# Power_Distribution_-_Pi.net
KiCad netlist of a schematic drawn in Altium Designer
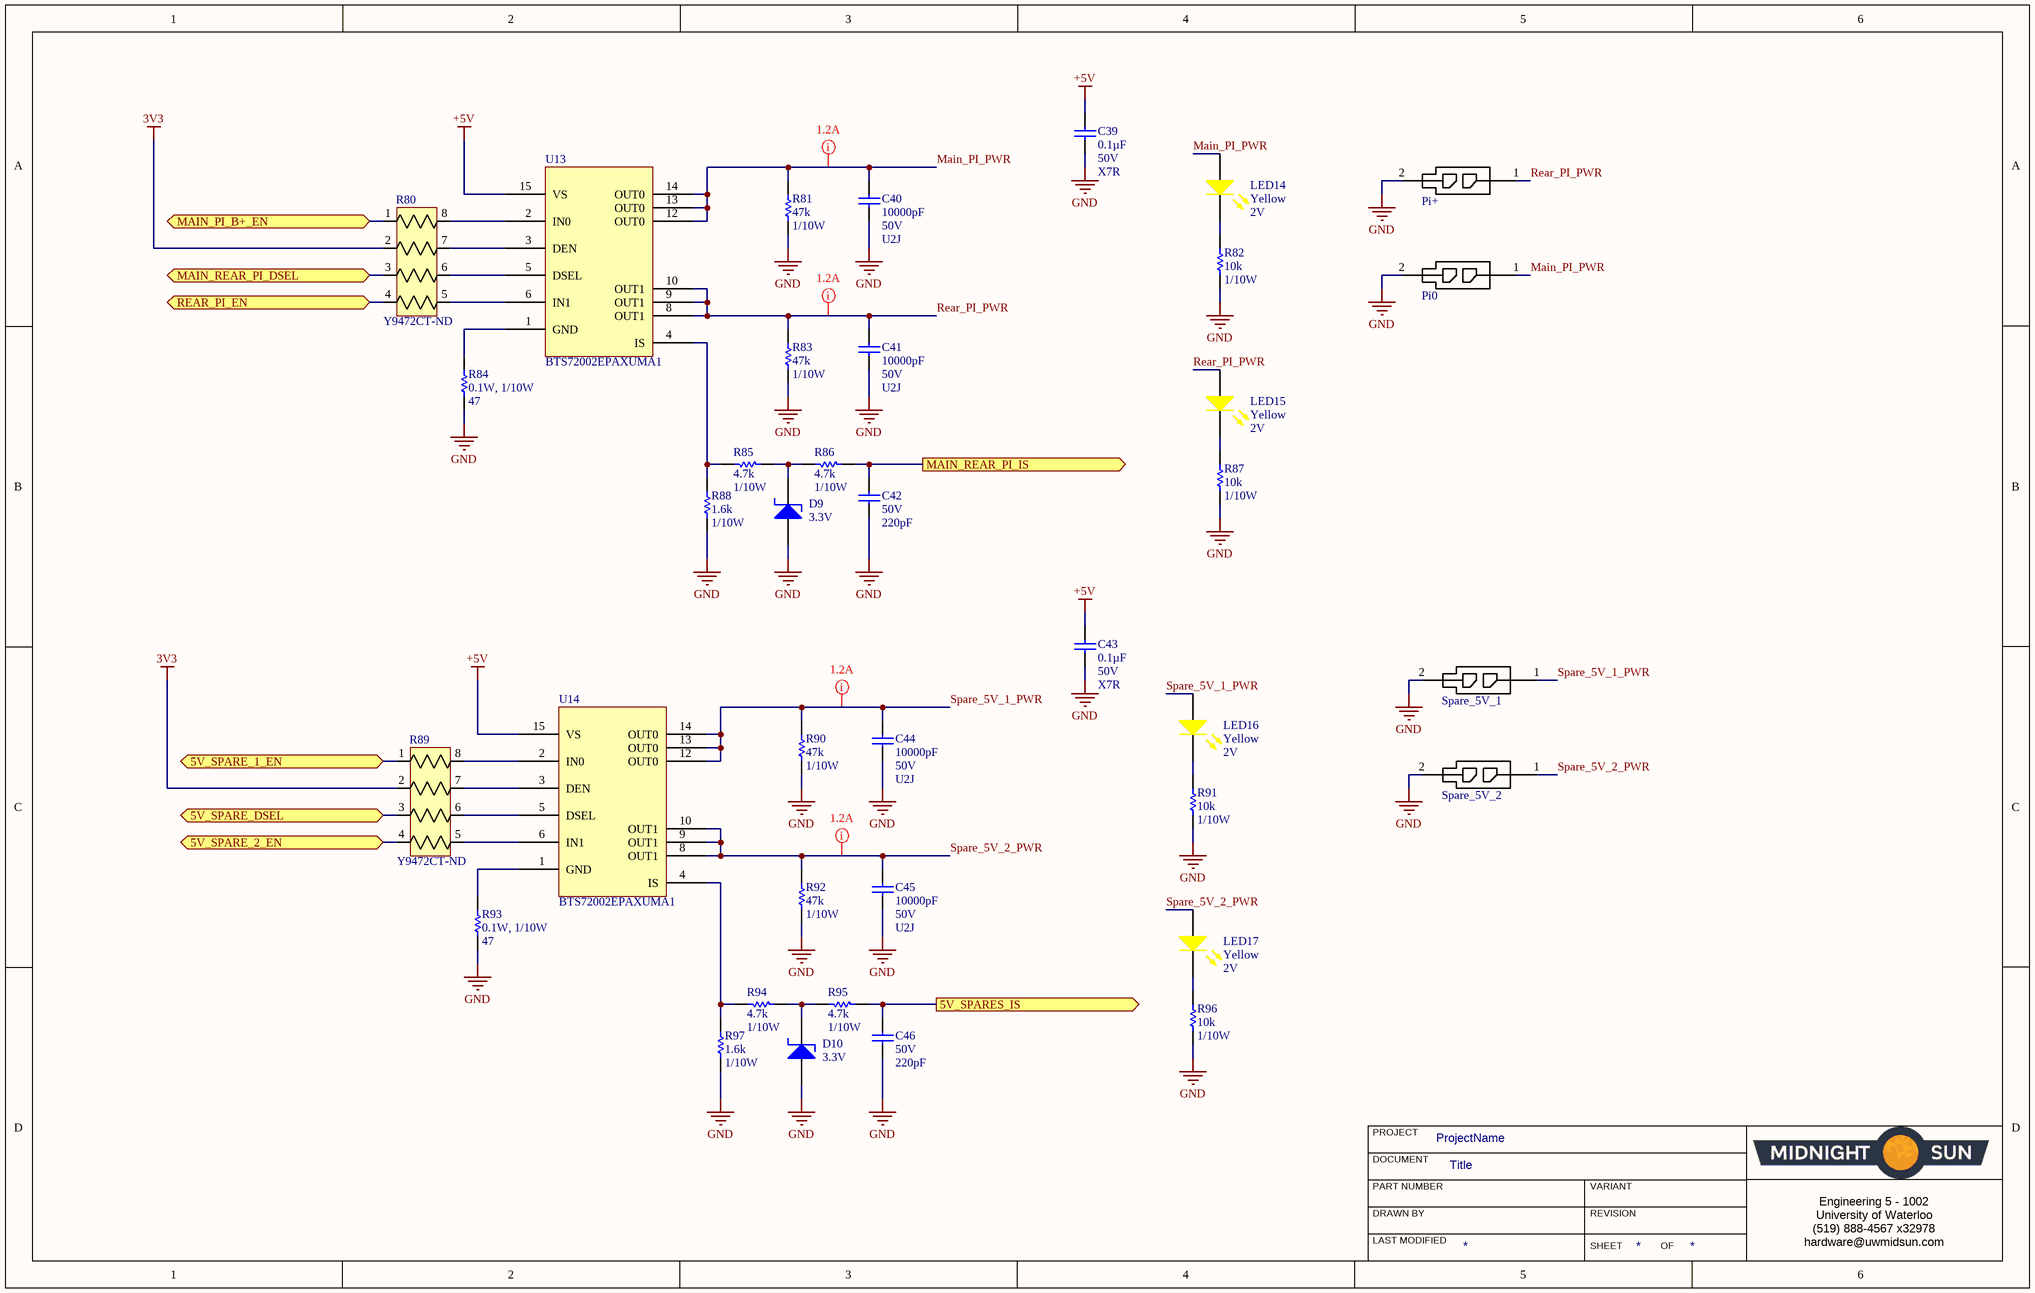
[diagram p0: Power Distribution - Pi.SchDoc]

(export (version "E")
  (design (tool "Eeschema 10.0.6"))
  (components
    (comp (ref "C39")
      (value "CAP CER 0.1UF 50V 10% X7R 0603")
      (footprint "CAP, 0603")
      (description "0.10µF ±10% 50V Ceramic Capacitor X7R 0603 (1608 Metric)")
      (fields
        (field (name "TOLERANCE") "±10%")
        (field (name "CAPACITANCE") "0.1µF")
        (field (name "VOLTAGE") "50V")
        (field (name "TEMPERATURE COEFFICIENT") "X7R")
      )
      (libsource (lib "Schematic Diagrams") (part "CAP CER 0.1UF 50V 10% X7R 0603"))
    )
    (comp (ref "C40")
      (value "CAP CER 10nF 50V 5% X7R 0603")
      (footprint "CAP, 0603")
      (description "10000pF ±5% 50V Ceramic Capacitor U2J 0603 (1608 Metric)")
      (fields
        (field (name "TOLERANCE") "±5%")
        (field (name "CAPACITANCE") "10000pF")
        (field (name "VOLTAGE") "50V")
        (field (name "TEMPERATURE COEFFICIENT") "U2J")
      )
      (libsource (lib "Schematic Diagrams") (part "CAP CER 10nF 50V 5% X7R 0603"))
    )
    (comp (ref "C41")
      (value "CAP CER 10nF 50V 5% X7R 0603")
      (footprint "CAP, 0603")
      (description "10000pF ±5% 50V Ceramic Capacitor U2J 0603 (1608 Metric)")
      (fields
        (field (name "TOLERANCE") "±5%")
        (field (name "CAPACITANCE") "10000pF")
        (field (name "VOLTAGE") "50V")
        (field (name "TEMPERATURE COEFFICIENT") "U2J")
      )
      (libsource (lib "Schematic Diagrams") (part "CAP CER 10nF 50V 5% X7R 0603"))
    )
    (comp (ref "C42")
      (value "CAP CER 220PF 50V C0G/NP0 0603")
      (footprint "CAP, 0603")
      (description "220pF ±5% 50V Ceramic Capacitor C0G, NP0 0603 (1608 Metric)")
      (fields
        (field (name "MANUFACTURER") "KEMET")
        (field (name "TOLERANCE") "5%")
        (field (name "VOLTAGE RATING") "50V")
        (field (name "CAPACITANCE") "220pF")
      )
      (libsource (lib "Schematic Diagrams") (part "CAP CER 220PF 50V C0G/NP0 0603"))
    )
    (comp (ref "C43")
      (value "CAP CER 0.1UF 50V 10% X7R 0603")
      (footprint "CAP, 0603")
      (description "0.10µF ±10% 50V Ceramic Capacitor X7R 0603 (1608 Metric)")
      (fields
        (field (name "TOLERANCE") "±10%")
        (field (name "CAPACITANCE") "0.1µF")
        (field (name "VOLTAGE") "50V")
        (field (name "TEMPERATURE COEFFICIENT") "X7R")
      )
      (libsource (lib "Schematic Diagrams") (part "CAP CER 0.1UF 50V 10% X7R 0603"))
    )
    (comp (ref "C44")
      (value "CAP CER 10nF 50V 5% X7R 0603")
      (footprint "CAP, 0603")
      (description "10000pF ±5% 50V Ceramic Capacitor U2J 0603 (1608 Metric)")
      (fields
        (field (name "TOLERANCE") "±5%")
        (field (name "CAPACITANCE") "10000pF")
        (field (name "VOLTAGE") "50V")
        (field (name "TEMPERATURE COEFFICIENT") "U2J")
      )
      (libsource (lib "Schematic Diagrams") (part "CAP CER 10nF 50V 5% X7R 0603"))
    )
    (comp (ref "C45")
      (value "CAP CER 10nF 50V 5% X7R 0603")
      (footprint "CAP, 0603")
      (description "10000pF ±5% 50V Ceramic Capacitor U2J 0603 (1608 Metric)")
      (fields
        (field (name "TOLERANCE") "±5%")
        (field (name "CAPACITANCE") "10000pF")
        (field (name "VOLTAGE") "50V")
        (field (name "TEMPERATURE COEFFICIENT") "U2J")
      )
      (libsource (lib "Schematic Diagrams") (part "CAP CER 10nF 50V 5% X7R 0603"))
    )
    (comp (ref "C46")
      (value "CAP CER 220PF 50V C0G/NP0 0603")
      (footprint "CAP, 0603")
      (description "220pF ±5% 50V Ceramic Capacitor C0G, NP0 0603 (1608 Metric)")
      (fields
        (field (name "MANUFACTURER") "KEMET")
        (field (name "TOLERANCE") "5%")
        (field (name "VOLTAGE RATING") "50V")
        (field (name "CAPACITANCE") "220pF")
      )
      (libsource (lib "Schematic Diagrams") (part "CAP CER 220PF 50V C0G/NP0 0603"))
    )
    (comp (ref "D9")
      (value "DIODE ZENER 3.3V 200MW SOD323")
      (footprint "sod-323")
      (description "Zener Diode 3.3V 200mW ±5% Surface Mount SOD-323")
      (fields (field (name "VOLTAGE") "3.3V"))
      (libsource (lib "Schematic Diagrams") (part "DIODE ZENER 3.3V 200MW SOD323"))
    )
    (comp (ref "D10")
      (value "DIODE ZENER 3.3V 200MW SOD323")
      (footprint "sod-323")
      (description "Zener Diode 3.3V 200mW ±5% Surface Mount SOD-323")
      (fields (field (name "VOLTAGE") "3.3V"))
      (libsource (lib "Schematic Diagrams") (part "DIODE ZENER 3.3V 200MW SOD323"))
    )
    (comp (ref "LED14")
      (value "LED YELLOW CLEAR 2.1V 0603")
      (footprint "LED_0603")
      (description "Yellow 590nm LED Indication - Discrete 2V 0603 (1608 Metric)")
      (fields
        (field (name "MANUFACTURER") "Wurth Electronics Inc.")
        (field (name "MANUFACTURER PART NUMBER") "150060YS75000")
        (field (name "COLOR") "Yellow")
        (field (name "VOLTAGE - FORWARD (VF) (TYP)") "2V")
      )
      (libsource (lib "Schematic Diagrams") (part "LED YELLOW CLEAR 2.1V 0603"))
    )
    (comp (ref "LED15")
      (value "LED YELLOW CLEAR 2.1V 0603")
      (footprint "LED_0603")
      (description "Yellow 590nm LED Indication - Discrete 2V 0603 (1608 Metric)")
      (fields
        (field (name "MANUFACTURER") "Wurth Electronics Inc.")
        (field (name "MANUFACTURER PART NUMBER") "150060YS75000")
        (field (name "COLOR") "Yellow")
        (field (name "VOLTAGE - FORWARD (VF) (TYP)") "2V")
      )
      (libsource (lib "Schematic Diagrams") (part "LED YELLOW CLEAR 2.1V 0603"))
    )
    (comp (ref "LED16")
      (value "LED YELLOW CLEAR 2.1V 0603")
      (footprint "LED_0603")
      (description "Yellow 590nm LED Indication - Discrete 2V 0603 (1608 Metric)")
      (fields
        (field (name "MANUFACTURER") "Wurth Electronics Inc.")
        (field (name "MANUFACTURER PART NUMBER") "150060YS75000")
        (field (name "COLOR") "Yellow")
        (field (name "VOLTAGE - FORWARD (VF) (TYP)") "2V")
      )
      (libsource (lib "Schematic Diagrams") (part "LED YELLOW CLEAR 2.1V 0603"))
    )
    (comp (ref "LED17")
      (value "LED YELLOW CLEAR 2.1V 0603")
      (footprint "LED_0603")
      (description "Yellow 590nm LED Indication - Discrete 2V 0603 (1608 Metric)")
      (fields
        (field (name "MANUFACTURER") "Wurth Electronics Inc.")
        (field (name "MANUFACTURER PART NUMBER") "150060YS75000")
        (field (name "COLOR") "Yellow")
        (field (name "VOLTAGE - FORWARD (VF) (TYP)") "2V")
      )
      (libsource (lib "Schematic Diagrams") (part "LED YELLOW CLEAR 2.1V 0603"))
    )
    (comp (ref "Pi+")
      (value "CONN 2POS MICRO-FIT 3mm")
      (footprint "CONN, 2POS MICRO-FIT")
      (description "Connector Header Through Hole 2 position")
      (fields (field (name "MANUFACTURER") "Molex") (field (name "MANUFACTURER PART NUMBER") "43045-0227"))
      (libsource (lib "Schematic Diagrams") (part "CONN 2POS MICRO-FIT 3mm"))
    )
    (comp (ref "Pi0")
      (value "CONN 2POS MICRO-FIT 3mm")
      (footprint "CONN, 2POS MICRO-FIT")
      (description "Connector Header Through Hole 2 position")
      (fields (field (name "MANUFACTURER") "Molex") (field (name "MANUFACTURER PART NUMBER") "43045-0227"))
      (libsource (lib "Schematic Diagrams") (part "CONN 2POS MICRO-FIT 3mm"))
    )
    (comp (ref "R80")
      (value "RES ARRAY 4 RES 4.7K OHM 1206")
      (footprint "RES ARRAY 4RES 1206")
      (fields (field (name "TOLERANCE") "±5%") (field (name "SUPPLIER PART NUMBER 1") "Y9472CT-ND"))
      (libsource (lib "Schematic Diagrams") (part "RES ARRAY 4 RES 4.7K OHM 1206"))
    )
    (comp (ref "R81")
      (value "RES 47K OHM 1% 1/10W 0603")
      (footprint "RES, 0603")
      (description "47 kOhms ±1% 0.1W, 1/10W Chip Resistor 0603 (1608 Metric) Automotive AEC-Q200 Thick Film")
      (fields
        (field (name "MANUFACTURER") "Panasonic")
        (field (name "MANUFACTURER PART NUMBER") "ERJ3EKF4702V")
        (field (name "RESISTANCE") "47k")
        (field (name "POWER RATING") "1/10W")
      )
      (libsource (lib "Schematic Diagrams") (part "RES 47K OHM 1% 1/10W 0603"))
    )
    (comp (ref "R82")
      (value "RES 10K OHM 1% 1/10W 0603")
      (footprint "RES, 0603")
      (description "RES SMD 10K OHM 1% 1/10W 0603")
      (fields
        (field (name "TOLERANCE") "±1%")
        (field (name "RESISTANCE") "10k")
        (field (name "POWER") "1/10W")
      )
      (libsource (lib "Schematic Diagrams") (part "RES 10K OHM 1% 1/10W 0603"))
    )
    (comp (ref "R83")
      (value "RES 47K OHM 1% 1/10W 0603")
      (footprint "RES, 0603")
      (description "47 kOhms ±1% 0.1W, 1/10W Chip Resistor 0603 (1608 Metric) Automotive AEC-Q200 Thick Film")
      (fields
        (field (name "MANUFACTURER") "Panasonic")
        (field (name "MANUFACTURER PART NUMBER") "ERJ3EKF4702V")
        (field (name "RESISTANCE") "47k")
        (field (name "POWER RATING") "1/10W")
      )
      (libsource (lib "Schematic Diagrams") (part "RES 47K OHM 1% 1/10W 0603"))
    )
    (comp (ref "R84")
      (value "RES SMD 47 OHM 1% 1/10W 0603")
      (footprint "RES, 0603")
      (fields
        (field (name "TOLERANCE") "±1%")
        (field (name "POWER (WATTS)") "0.1W, 1/10W")
        (field (name "VALUES") "47")
      )
      (libsource (lib "Schematic Diagrams") (part "RES SMD 47 OHM 1% 1/10W 0603"))
    )
    (comp (ref "R85")
      (value "RES 4.7K OHM 1% 1/10W 0603")
      (footprint "RES, 0603")
      (description "4.7k Ohm ±1% 0.1W, 1/10W Chip Resistor 0603 (1608 Metric) Moisture Resistant Thick Film")
      (fields
        (field (name "TOLERANCE") "±1%")
        (field (name "RESISTANCE (OHMS)") "4.7k")
        (field (name "POWER (WATTS)") "1/10W")
      )
      (libsource (lib "Schematic Diagrams") (part "RES 4.7K OHM 1% 1/10W 0603"))
    )
    (comp (ref "R86")
      (value "RES 4.7K OHM 1% 1/10W 0603")
      (footprint "RES, 0603")
      (description "4.7k Ohm ±1% 0.1W, 1/10W Chip Resistor 0603 (1608 Metric) Moisture Resistant Thick Film")
      (fields
        (field (name "TOLERANCE") "±1%")
        (field (name "RESISTANCE (OHMS)") "4.7k")
        (field (name "POWER (WATTS)") "1/10W")
      )
      (libsource (lib "Schematic Diagrams") (part "RES 4.7K OHM 1% 1/10W 0603"))
    )
    (comp (ref "R87")
      (value "RES 10K OHM 1% 1/10W 0603")
      (footprint "RES, 0603")
      (description "RES SMD 10K OHM 1% 1/10W 0603")
      (fields
        (field (name "TOLERANCE") "±1%")
        (field (name "RESISTANCE") "10k")
        (field (name "POWER") "1/10W")
      )
      (libsource (lib "Schematic Diagrams") (part "RES 10K OHM 1% 1/10W 0603"))
    )
    (comp (ref "R88")
      (value "RES 1.6K OHM 1% 1/10W 0603")
      (footprint "RES, 0603")
      (description "1.6 kOhms ±1% 0.1W, 1/10W Chip Resistor 0603 (1608 Metric) Moisture Resistant Thick Film")
      (fields
        (field (name "MANUFACTURER") "Yageo")
        (field (name "MANUFACTURER PART NUMBER") "RC0603FR-071K6L")
        (field (name "RESISTANCE") "1.6k")
        (field (name "POWER RATING") "1/10W")
      )
      (libsource (lib "Schematic Diagrams") (part "RES 1.6K OHM 1% 1/10W 0603"))
    )
    (comp (ref "R89")
      (value "RES ARRAY 4 RES 4.7K OHM 1206")
      (footprint "RES ARRAY 4RES 1206")
      (fields (field (name "TOLERANCE") "±5%") (field (name "SUPPLIER PART NUMBER 1") "Y9472CT-ND"))
      (libsource (lib "Schematic Diagrams") (part "RES ARRAY 4 RES 4.7K OHM 1206"))
    )
    (comp (ref "R90")
      (value "RES 47K OHM 1% 1/10W 0603")
      (footprint "RES, 0603")
      (description "47 kOhms ±1% 0.1W, 1/10W Chip Resistor 0603 (1608 Metric) Automotive AEC-Q200 Thick Film")
      (fields
        (field (name "MANUFACTURER") "Panasonic")
        (field (name "MANUFACTURER PART NUMBER") "ERJ3EKF4702V")
        (field (name "RESISTANCE") "47k")
        (field (name "POWER RATING") "1/10W")
      )
      (libsource (lib "Schematic Diagrams") (part "RES 47K OHM 1% 1/10W 0603"))
    )
    (comp (ref "R91")
      (value "RES 10K OHM 1% 1/10W 0603")
      (footprint "RES, 0603")
      (description "RES SMD 10K OHM 1% 1/10W 0603")
      (fields
        (field (name "TOLERANCE") "±1%")
        (field (name "RESISTANCE") "10k")
        (field (name "POWER") "1/10W")
      )
      (libsource (lib "Schematic Diagrams") (part "RES 10K OHM 1% 1/10W 0603"))
    )
    (comp (ref "R92")
      (value "RES 47K OHM 1% 1/10W 0603")
      (footprint "RES, 0603")
      (description "47 kOhms ±1% 0.1W, 1/10W Chip Resistor 0603 (1608 Metric) Automotive AEC-Q200 Thick Film")
      (fields
        (field (name "MANUFACTURER") "Panasonic")
        (field (name "MANUFACTURER PART NUMBER") "ERJ3EKF4702V")
        (field (name "RESISTANCE") "47k")
        (field (name "POWER RATING") "1/10W")
      )
      (libsource (lib "Schematic Diagrams") (part "RES 47K OHM 1% 1/10W 0603"))
    )
    (comp (ref "R93")
      (value "RES SMD 47 OHM 1% 1/10W 0603")
      (footprint "RES, 0603")
      (fields
        (field (name "TOLERANCE") "±1%")
        (field (name "POWER (WATTS)") "0.1W, 1/10W")
        (field (name "VALUES") "47")
      )
      (libsource (lib "Schematic Diagrams") (part "RES SMD 47 OHM 1% 1/10W 0603"))
    )
    (comp (ref "R94")
      (value "RES 4.7K OHM 1% 1/10W 0603")
      (footprint "RES, 0603")
      (description "4.7k Ohm ±1% 0.1W, 1/10W Chip Resistor 0603 (1608 Metric) Moisture Resistant Thick Film")
      (fields
        (field (name "TOLERANCE") "±1%")
        (field (name "RESISTANCE (OHMS)") "4.7k")
        (field (name "POWER (WATTS)") "1/10W")
      )
      (libsource (lib "Schematic Diagrams") (part "RES 4.7K OHM 1% 1/10W 0603"))
    )
    (comp (ref "R95")
      (value "RES 4.7K OHM 1% 1/10W 0603")
      (footprint "RES, 0603")
      (description "4.7k Ohm ±1% 0.1W, 1/10W Chip Resistor 0603 (1608 Metric) Moisture Resistant Thick Film")
      (fields
        (field (name "TOLERANCE") "±1%")
        (field (name "RESISTANCE (OHMS)") "4.7k")
        (field (name "POWER (WATTS)") "1/10W")
      )
      (libsource (lib "Schematic Diagrams") (part "RES 4.7K OHM 1% 1/10W 0603"))
    )
    (comp (ref "R96")
      (value "RES 10K OHM 1% 1/10W 0603")
      (footprint "RES, 0603")
      (description "RES SMD 10K OHM 1% 1/10W 0603")
      (fields
        (field (name "TOLERANCE") "±1%")
        (field (name "RESISTANCE") "10k")
        (field (name "POWER") "1/10W")
      )
      (libsource (lib "Schematic Diagrams") (part "RES 10K OHM 1% 1/10W 0603"))
    )
    (comp (ref "R97")
      (value "RES 1.6K OHM 1% 1/10W 0603")
      (footprint "RES, 0603")
      (description "1.6 kOhms ±1% 0.1W, 1/10W Chip Resistor 0603 (1608 Metric) Moisture Resistant Thick Film")
      (fields
        (field (name "MANUFACTURER") "Yageo")
        (field (name "MANUFACTURER PART NUMBER") "RC0603FR-071K6L")
        (field (name "RESISTANCE") "1.6k")
        (field (name "POWER RATING") "1/10W")
      )
      (libsource (lib "Schematic Diagrams") (part "RES 1.6K OHM 1% 1/10W 0603"))
    )
    (comp (ref "Spare_5V_1")
      (value "CONN 2POS MICRO-FIT 3mm")
      (footprint "CONN, 2POS MICRO-FIT")
      (description "Connector Header Through Hole 2 position")
      (fields (field (name "MANUFACTURER") "Molex") (field (name "MANUFACTURER PART NUMBER") "43045-0227"))
      (libsource (lib "Schematic Diagrams") (part "CONN 2POS MICRO-FIT 3mm"))
    )
    (comp (ref "Spare_5V_2")
      (value "CONN 2POS MICRO-FIT 3mm")
      (footprint "CONN, 2POS MICRO-FIT")
      (description "Connector Header Through Hole 2 position")
      (fields (field (name "MANUFACTURER") "Molex") (field (name "MANUFACTURER PART NUMBER") "43045-0227"))
      (libsource (lib "Schematic Diagrams") (part "CONN 2POS MICRO-FIT 3mm"))
    )
    (comp (ref "U13")
      (value "IC LOAD SWITCH BTS7200-2EPA PG-TSDSO-14_1")
      (footprint "IC LOAD SWITCH PG-TSDSO-14-22")
      (description "Power Switch/Driver 1:1 N-Channel 1.2A PG-TSDSO-14-22")
      (fields
        (field (name "MANUFACTURER") "Infineon")
        (field (name "MANUFACTURER PART NUMBER") "BTS72002EPAXUMA1")
      )
      (libsource (lib "Schematic Diagrams") (part "IC LOAD SWITCH BTS7200-2EPA PG-TSDSO-14_1"))
    )
    (comp (ref "U14")
      (value "IC LOAD SWITCH BTS7200-2EPA PG-TSDSO-14_1")
      (footprint "IC LOAD SWITCH PG-TSDSO-14-22")
      (description "Power Switch/Driver 1:1 N-Channel 1.2A PG-TSDSO-14-22")
      (fields
        (field (name "MANUFACTURER") "Infineon")
        (field (name "MANUFACTURER PART NUMBER") "BTS72002EPAXUMA1")
      )
      (libsource (lib "Schematic Diagrams") (part "IC LOAD SWITCH BTS7200-2EPA PG-TSDSO-14_1"))
    )
  )
  (nets
    (net (code "1") (name "+5V") (class "Default")
      (node (ref "C39") (pin "1") (pinfunction "1_1") (pintype "passive"))
      (node (ref "C43") (pin "1") (pinfunction "1_1") (pintype "passive"))
      (node (ref "U13") (pin "15") (pinfunction "VS_15") (pintype "passive"))
      (node (ref "U14") (pin "15") (pinfunction "VS_15") (pintype "passive"))
    )
    (net (code "2") (name "/5V_SPARES_IS") (class "Default")
      (node (ref "C46") (pin "1") (pinfunction "1_1") (pintype "passive"))
      (node (ref "R95") (pin "1") (pinfunction "1_1") (pintype "passive"))
    )
    (net (code "3") (name "/5V_SPARE_1_EN") (class "Default")
      (node (ref "R89") (pin "1") (pinfunction "1_1") (pintype "passive"))
    )
    (net (code "4") (name "/5V_SPARE_2_EN") (class "Default")
      (node (ref "R89") (pin "4") (pinfunction "4_4") (pintype "passive"))
    )
    (net (code "5") (name "/5V_SPARE_DSEL") (class "Default")
      (node (ref "R89") (pin "3") (pinfunction "3_3") (pintype "passive"))
    )
    (net (code "6") (name "/MAIN_PI_B+_EN") (class "Default")
      (node (ref "R80") (pin "1") (pinfunction "1_1") (pintype "passive"))
    )
    (net (code "7") (name "/MAIN_REAR_PI_DSEL") (class "Default")
      (node (ref "R80") (pin "3") (pinfunction "3_3") (pintype "passive"))
    )
    (net (code "8") (name "/MAIN_REAR_PI_IS") (class "Default")
      (node (ref "C42") (pin "1") (pinfunction "1_1") (pintype "passive"))
      (node (ref "R86") (pin "1") (pinfunction "1_1") (pintype "passive"))
    )
    (net (code "9") (name "/Main_PI_PWR") (class "Default")
      (node (ref "C40") (pin "1") (pinfunction "1_1") (pintype "passive"))
      (node (ref "LED14") (pin "1") (pinfunction "A_1") (pintype "passive"))
      (node (ref "Pi0") (pin "1") (pinfunction "1_1") (pintype "passive"))
      (node (ref "R81") (pin "1") (pinfunction "1_1") (pintype "passive"))
      (node (ref "U13") (pin "12") (pinfunction "OUT0_12") (pintype "passive"))
      (node (ref "U13") (pin "13") (pinfunction "OUT0_13") (pintype "passive"))
      (node (ref "U13") (pin "14") (pinfunction "OUT0_14") (pintype "passive"))
    )
    (net (code "10") (name "/REAR_PI_EN") (class "Default")
      (node (ref "R80") (pin "4") (pinfunction "4_4") (pintype "passive"))
    )
    (net (code "11") (name "/Rear_PI_PWR") (class "Default")
      (node (ref "C41") (pin "1") (pinfunction "1_1") (pintype "passive"))
      (node (ref "LED15") (pin "1") (pinfunction "A_1") (pintype "passive"))
      (node (ref "Pi+") (pin "1") (pinfunction "1_1") (pintype "passive"))
      (node (ref "R83") (pin "1") (pinfunction "1_1") (pintype "passive"))
      (node (ref "U13") (pin "10") (pinfunction "OUT1_10") (pintype "passive"))
      (node (ref "U13") (pin "8") (pinfunction "OUT1_8") (pintype "passive"))
      (node (ref "U13") (pin "9") (pinfunction "OUT1_9") (pintype "passive"))
    )
    (net (code "12") (name "/Spare_5V_1_PWR") (class "Default")
      (node (ref "C44") (pin "1") (pinfunction "1_1") (pintype "passive"))
      (node (ref "LED16") (pin "1") (pinfunction "A_1") (pintype "passive"))
      (node (ref "R90") (pin "1") (pinfunction "1_1") (pintype "passive"))
      (node (ref "Spare_5V_1") (pin "1") (pinfunction "1_1") (pintype "passive"))
      (node (ref "U14") (pin "12") (pinfunction "OUT0_12") (pintype "passive"))
      (node (ref "U14") (pin "13") (pinfunction "OUT0_13") (pintype "passive"))
      (node (ref "U14") (pin "14") (pinfunction "OUT0_14") (pintype "passive"))
    )
    (net (code "13") (name "/Spare_5V_2_PWR") (class "Default")
      (node (ref "C45") (pin "1") (pinfunction "1_1") (pintype "passive"))
      (node (ref "LED17") (pin "1") (pinfunction "A_1") (pintype "passive"))
      (node (ref "R92") (pin "1") (pinfunction "1_1") (pintype "passive"))
      (node (ref "Spare_5V_2") (pin "1") (pinfunction "1_1") (pintype "passive"))
      (node (ref "U14") (pin "10") (pinfunction "OUT1_10") (pintype "passive"))
      (node (ref "U14") (pin "8") (pinfunction "OUT1_8") (pintype "passive"))
      (node (ref "U14") (pin "9") (pinfunction "OUT1_9") (pintype "passive"))
    )
    (net (code "14") (name "3V3") (class "Default")
      (node (ref "R80") (pin "2") (pinfunction "2_2") (pintype "passive"))
      (node (ref "R89") (pin "2") (pinfunction "2_2") (pintype "passive"))
    )
    (net (code "15") (name "GND") (class "Default")
      (node (ref "C39") (pin "2") (pinfunction "2_2") (pintype "passive"))
      (node (ref "C40") (pin "2") (pinfunction "2_2") (pintype "passive"))
      (node (ref "C41") (pin "2") (pinfunction "2_2") (pintype "passive"))
      (node (ref "C42") (pin "2") (pinfunction "2_2") (pintype "passive"))
      (node (ref "C43") (pin "2") (pinfunction "2_2") (pintype "passive"))
      (node (ref "C44") (pin "2") (pinfunction "2_2") (pintype "passive"))
      (node (ref "C45") (pin "2") (pinfunction "2_2") (pintype "passive"))
      (node (ref "C46") (pin "2") (pinfunction "2_2") (pintype "passive"))
      (node (ref "D10") (pin "1") (pinfunction "A_1") (pintype "passive"))
      (node (ref "D9") (pin "1") (pinfunction "A_1") (pintype "passive"))
      (node (ref "Pi+") (pin "2") (pinfunction "2_2") (pintype "passive"))
      (node (ref "Pi0") (pin "2") (pinfunction "2_2") (pintype "passive"))
      (node (ref "R81") (pin "2") (pinfunction "2_2") (pintype "passive"))
      (node (ref "R82") (pin "2") (pinfunction "2_2") (pintype "passive"))
      (node (ref "R83") (pin "2") (pinfunction "2_2") (pintype "passive"))
      (node (ref "R84") (pin "2") (pinfunction "2_2") (pintype "passive"))
      (node (ref "R87") (pin "2") (pinfunction "2_2") (pintype "passive"))
      (node (ref "R88") (pin "2") (pinfunction "2_2") (pintype "passive"))
      (node (ref "R90") (pin "2") (pinfunction "2_2") (pintype "passive"))
      (node (ref "R91") (pin "2") (pinfunction "2_2") (pintype "passive"))
      (node (ref "R92") (pin "2") (pinfunction "2_2") (pintype "passive"))
      (node (ref "R93") (pin "2") (pinfunction "2_2") (pintype "passive"))
      (node (ref "R96") (pin "2") (pinfunction "2_2") (pintype "passive"))
      (node (ref "R97") (pin "2") (pinfunction "2_2") (pintype "passive"))
      (node (ref "Spare_5V_1") (pin "2") (pinfunction "2_2") (pintype "passive"))
      (node (ref "Spare_5V_2") (pin "2") (pinfunction "2_2") (pintype "passive"))
    )
    (net (code "16") (name "Net-(D9-K)") (class "Default")
      (node (ref "D9") (pin "2") (pinfunction "K_2") (pintype "passive"))
      (node (ref "R85") (pin "1") (pinfunction "1_1") (pintype "passive"))
      (node (ref "R86") (pin "2") (pinfunction "2_2") (pintype "passive"))
    )
    (net (code "17") (name "Net-(D10-K)") (class "Default")
      (node (ref "D10") (pin "2") (pinfunction "K_2") (pintype "passive"))
      (node (ref "R94") (pin "1") (pinfunction "1_1") (pintype "passive"))
      (node (ref "R95") (pin "2") (pinfunction "2_2") (pintype "passive"))
    )
    (net (code "18") (name "Net-(LED14-K)") (class "Default")
      (node (ref "LED14") (pin "2") (pinfunction "K_2") (pintype "passive"))
      (node (ref "R82") (pin "1") (pinfunction "1_1") (pintype "passive"))
    )
    (net (code "19") (name "Net-(LED15-K)") (class "Default")
      (node (ref "LED15") (pin "2") (pinfunction "K_2") (pintype "passive"))
      (node (ref "R87") (pin "1") (pinfunction "1_1") (pintype "passive"))
    )
    (net (code "20") (name "Net-(LED16-K)") (class "Default")
      (node (ref "LED16") (pin "2") (pinfunction "K_2") (pintype "passive"))
      (node (ref "R91") (pin "1") (pinfunction "1_1") (pintype "passive"))
    )
    (net (code "21") (name "Net-(LED17-K)") (class "Default")
      (node (ref "LED17") (pin "2") (pinfunction "K_2") (pintype "passive"))
      (node (ref "R96") (pin "1") (pinfunction "1_1") (pintype "passive"))
    )
    (net (code "22") (name "Net-(U13-DEN)") (class "Default")
      (node (ref "R80") (pin "7") (pinfunction "7_7") (pintype "passive"))
      (node (ref "U13") (pin "3") (pinfunction "DEN_3") (pintype "passive"))
    )
    (net (code "23") (name "Net-(U13-DSEL)") (class "Default")
      (node (ref "R80") (pin "6") (pinfunction "6_6") (pintype "passive"))
      (node (ref "U13") (pin "5") (pinfunction "DSEL_5") (pintype "passive"))
    )
    (net (code "24") (name "Net-(U13-GND)") (class "Default")
      (node (ref "R84") (pin "1") (pinfunction "1_1") (pintype "passive"))
      (node (ref "U13") (pin "1") (pinfunction "GND_1") (pintype "passive"))
    )
    (net (code "25") (name "Net-(U13-IN0)") (class "Default")
      (node (ref "R80") (pin "8") (pinfunction "8_8") (pintype "passive"))
      (node (ref "U13") (pin "2") (pinfunction "IN0_2") (pintype "passive"))
    )
    (net (code "26") (name "Net-(U13-IN1)") (class "Default")
      (node (ref "R80") (pin "5") (pinfunction "5_5") (pintype "passive"))
      (node (ref "U13") (pin "6") (pinfunction "IN1_6") (pintype "passive"))
    )
    (net (code "27") (name "Net-(U13-IS)") (class "Default")
      (node (ref "R85") (pin "2") (pinfunction "2_2") (pintype "passive"))
      (node (ref "R88") (pin "1") (pinfunction "1_1") (pintype "passive"))
      (node (ref "U13") (pin "4") (pinfunction "IS_4") (pintype "passive"))
    )
    (net (code "28") (name "Net-(U14-DEN)") (class "Default")
      (node (ref "R89") (pin "7") (pinfunction "7_7") (pintype "passive"))
      (node (ref "U14") (pin "3") (pinfunction "DEN_3") (pintype "passive"))
    )
    (net (code "29") (name "Net-(U14-DSEL)") (class "Default")
      (node (ref "R89") (pin "6") (pinfunction "6_6") (pintype "passive"))
      (node (ref "U14") (pin "5") (pinfunction "DSEL_5") (pintype "passive"))
    )
    (net (code "30") (name "Net-(U14-GND)") (class "Default")
      (node (ref "R93") (pin "1") (pinfunction "1_1") (pintype "passive"))
      (node (ref "U14") (pin "1") (pinfunction "GND_1") (pintype "passive"))
    )
    (net (code "31") (name "Net-(U14-IN0)") (class "Default")
      (node (ref "R89") (pin "8") (pinfunction "8_8") (pintype "passive"))
      (node (ref "U14") (pin "2") (pinfunction "IN0_2") (pintype "passive"))
    )
    (net (code "32") (name "Net-(U14-IN1)") (class "Default")
      (node (ref "R89") (pin "5") (pinfunction "5_5") (pintype "passive"))
      (node (ref "U14") (pin "6") (pinfunction "IN1_6") (pintype "passive"))
    )
    (net (code "33") (name "Net-(U14-IS)") (class "Default")
      (node (ref "R94") (pin "2") (pinfunction "2_2") (pintype "passive"))
      (node (ref "R97") (pin "1") (pinfunction "1_1") (pintype "passive"))
      (node (ref "U14") (pin "4") (pinfunction "IS_4") (pintype "passive"))
    )
  )
)
